# rov_control.net
KiCad netlist of a schematic drawn in EAGLE
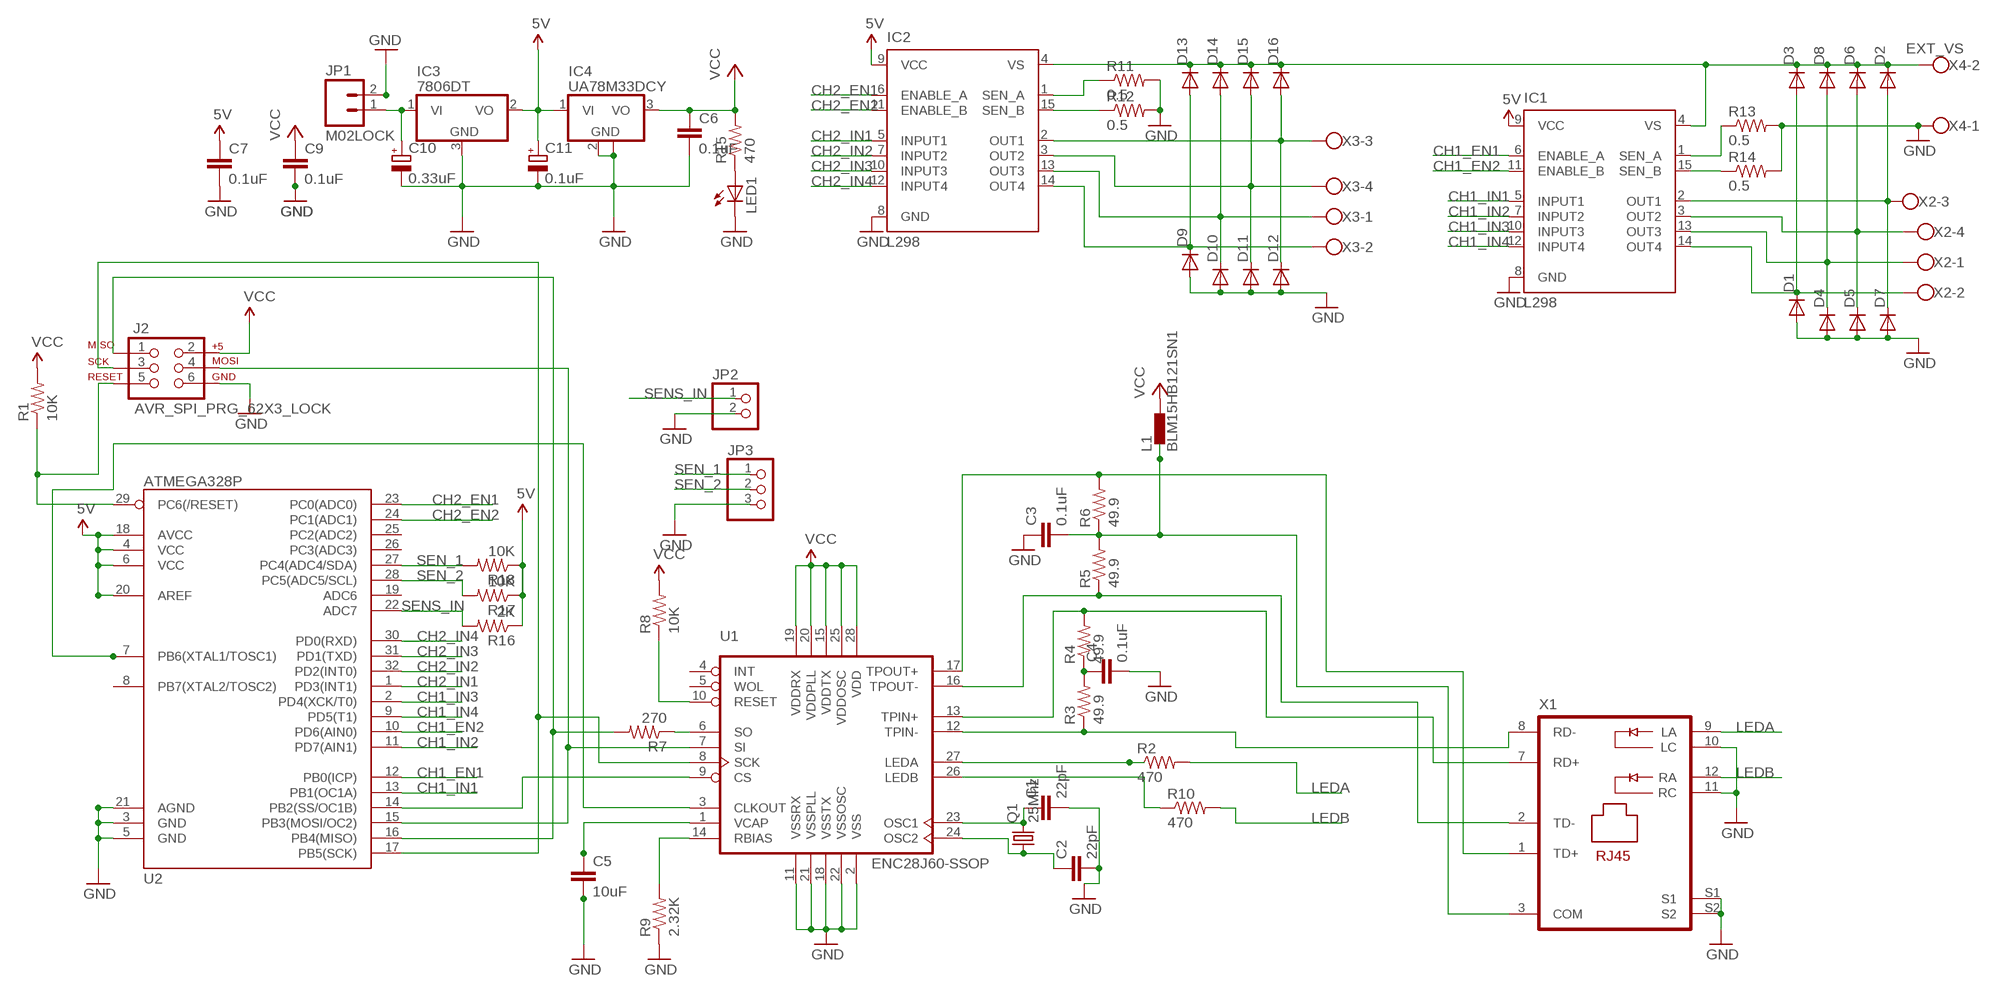
[diagram p0: schematic, sheet 1]

(export (version "E")
  (design (tool "Eeschema 10.0.6"))
  (components
    (comp (ref "C1")
      (value "22pF")
      (footprint "eagle-import:0805")
      (libsource (lib "eagle-import") (part "CAP0805"))
    )
    (comp (ref "C2")
      (value "22pF")
      (footprint "eagle-import:0805")
      (libsource (lib "eagle-import") (part "CAP0805"))
    )
    (comp (ref "C3")
      (value "0.1uF")
      (footprint "eagle-import:0805")
      (libsource (lib "eagle-import") (part "CAP0805"))
    )
    (comp (ref "C4")
      (value "0.1uF")
      (footprint "eagle-import:0805")
      (libsource (lib "eagle-import") (part "CAP0805"))
    )
    (comp (ref "C5")
      (value "10uF")
      (footprint "eagle-import:0805")
      (libsource (lib "eagle-import") (part "CAP0805"))
    )
    (comp (ref "C6")
      (value "0.1uF")
      (footprint "eagle-import:0805")
      (libsource (lib "eagle-import") (part "SparkFun-Passives_CAP0805"))
    )
    (comp (ref "C7")
      (value "0.1uF")
      (footprint "eagle-import:0805")
      (libsource (lib "eagle-import") (part "CAP0805"))
    )
    (comp (ref "C9")
      (value "0.1uF")
      (footprint "eagle-import:0805")
      (libsource (lib "eagle-import") (part "CAP0805"))
    )
    (comp (ref "C10")
      (value "0.33uF")
      (footprint "eagle-import:PANASONIC_A")
      (libsource (lib "eagle-import") (part "CPOL-EUA"))
    )
    (comp (ref "C11")
      (value "0.1uF")
      (footprint "eagle-import:PANASONIC_A")
      (libsource (lib "eagle-import") (part "CPOL-EUA"))
    )
    (comp (ref "D1")
      (value "DIODESMA")
      (footprint "eagle-import:SMA-DIODE")
      (libsource (lib "eagle-import") (part "DIODESMA"))
    )
    (comp (ref "D2")
      (value "DIODESMA")
      (footprint "eagle-import:SMA-DIODE")
      (libsource (lib "eagle-import") (part "DIODESMA"))
    )
    (comp (ref "D3")
      (value "DIODESMA")
      (footprint "eagle-import:SMA-DIODE")
      (libsource (lib "eagle-import") (part "DIODESMA"))
    )
    (comp (ref "D4")
      (value "DIODESMA")
      (footprint "eagle-import:SMA-DIODE")
      (libsource (lib "eagle-import") (part "DIODESMA"))
    )
    (comp (ref "D5")
      (value "DIODESMA")
      (footprint "eagle-import:SMA-DIODE")
      (libsource (lib "eagle-import") (part "DIODESMA"))
    )
    (comp (ref "D6")
      (value "DIODESMA")
      (footprint "eagle-import:SMA-DIODE")
      (libsource (lib "eagle-import") (part "DIODESMA"))
    )
    (comp (ref "D7")
      (value "DIODESMA")
      (footprint "eagle-import:SMA-DIODE")
      (libsource (lib "eagle-import") (part "DIODESMA"))
    )
    (comp (ref "D8")
      (value "DIODESMA")
      (footprint "eagle-import:SMA-DIODE")
      (libsource (lib "eagle-import") (part "DIODESMA"))
    )
    (comp (ref "D9")
      (value "DIODESMA")
      (footprint "eagle-import:SMA-DIODE")
      (libsource (lib "eagle-import") (part "DIODESMA"))
    )
    (comp (ref "D10")
      (value "DIODESMA")
      (footprint "eagle-import:SMA-DIODE")
      (libsource (lib "eagle-import") (part "DIODESMA"))
    )
    (comp (ref "D11")
      (value "DIODESMA")
      (footprint "eagle-import:SMA-DIODE")
      (libsource (lib "eagle-import") (part "DIODESMA"))
    )
    (comp (ref "D12")
      (value "DIODESMA")
      (footprint "eagle-import:SMA-DIODE")
      (libsource (lib "eagle-import") (part "DIODESMA"))
    )
    (comp (ref "D13")
      (value "DIODESMA")
      (footprint "eagle-import:SMA-DIODE")
      (libsource (lib "eagle-import") (part "DIODESMA"))
    )
    (comp (ref "D14")
      (value "DIODESMA")
      (footprint "eagle-import:SMA-DIODE")
      (libsource (lib "eagle-import") (part "DIODESMA"))
    )
    (comp (ref "D15")
      (value "DIODESMA")
      (footprint "eagle-import:SMA-DIODE")
      (libsource (lib "eagle-import") (part "DIODESMA"))
    )
    (comp (ref "D16")
      (value "DIODESMA")
      (footprint "eagle-import:SMA-DIODE")
      (libsource (lib "eagle-import") (part "DIODESMA"))
    )
    (comp (ref "IC1")
      (value "L298")
      (footprint "eagle-import:MULTIWATT-15")
      (fields (field (name "MPN") "L298N"))
      (libsource (lib "eagle-import") (part "L298"))
    )
    (comp (ref "IC2")
      (value "L298")
      (footprint "eagle-import:MULTIWATT-15")
      (fields (field (name "MPN") "L298N"))
      (libsource (lib "eagle-import") (part "L298"))
    )
    (comp (ref "IC3")
      (value "7806DT")
      (footprint "eagle-import:TO252")
      (libsource (lib "eagle-import") (part "78DT06"))
    )
    (comp (ref "IC4")
      (value "UA78M33DCY")
      (footprint "eagle-import:SOT223")
      (libsource (lib "eagle-import") (part "UA78MDCY33"))
    )
    (comp (ref "J2")
      (value "AVR_SPI_PRG_62X3_LOCK")
      (footprint "eagle-import:2X3_LOCK")
      (libsource (lib "eagle-import") (part "AVR_SPI_PRG_62X3_LOCK"))
    )
    (comp (ref "JP1")
      (value "M02LOCK")
      (footprint "eagle-import:1X02_LOCK")
      (libsource (lib "eagle-import") (part "M02LOCK"))
    )
    (comp (ref "JP2")
      (value "PINHD-1X2")
      (footprint "eagle-import:1X02")
      (libsource (lib "eagle-import") (part "PINHD-1X2"))
    )
    (comp (ref "JP3")
      (value "PINHD-1X3")
      (footprint "eagle-import:1X03")
      (libsource (lib "eagle-import") (part "PINHD-1X3"))
    )
    (comp (ref "L1")
      (value "BLM15HB121SN1")
      (footprint "eagle-import:0402")
      (libsource (lib "eagle-import") (part "BLM15HB121SN1"))
    )
    (comp (ref "LED1")
      (value "LEDSML0805")
      (footprint "eagle-import:SML0805")
      (libsource (lib "eagle-import") (part "LEDSML0805"))
    )
    (comp (ref "Q1")
      (value "25Mhz")
      (footprint "eagle-import:HC49UP")
      (libsource (lib "eagle-import") (part "CRYSTALHC49UP"))
    )
    (comp (ref "R1")
      (value "10K")
      (footprint "eagle-import:0805")
      (libsource (lib "eagle-import") (part "SparkFun-Resistors_RESISTOR0805-RES"))
    )
    (comp (ref "R2")
      (value "470")
      (footprint "eagle-import:0805")
      (libsource (lib "eagle-import") (part "RESISTOR0805-RES"))
    )
    (comp (ref "R3")
      (value "49.9")
      (footprint "eagle-import:0805")
      (libsource (lib "eagle-import") (part "SparkFun-Resistors_RESISTOR0805-RES"))
    )
    (comp (ref "R4")
      (value "49.9")
      (footprint "eagle-import:0805")
      (libsource (lib "eagle-import") (part "SparkFun-Resistors_RESISTOR0805-RES"))
    )
    (comp (ref "R5")
      (value "49.9")
      (footprint "eagle-import:0805")
      (libsource (lib "eagle-import") (part "RESISTOR0805-RES"))
    )
    (comp (ref "R6")
      (value "49.9")
      (footprint "eagle-import:0805")
      (libsource (lib "eagle-import") (part "RESISTOR0805-RES"))
    )
    (comp (ref "R7")
      (value "270")
      (footprint "eagle-import:0805")
      (libsource (lib "eagle-import") (part "SparkFun-Resistors_RESISTOR0805-RES"))
    )
    (comp (ref "R8")
      (value "10K")
      (footprint "eagle-import:0805")
      (libsource (lib "eagle-import") (part "RESISTOR0805-RES"))
    )
    (comp (ref "R9")
      (value "2.32K")
      (footprint "eagle-import:0805")
      (libsource (lib "eagle-import") (part "RESISTOR0805-RES"))
    )
    (comp (ref "R10")
      (value "470")
      (footprint "eagle-import:0805")
      (libsource (lib "eagle-import") (part "RESISTOR0805-RES"))
    )
    (comp (ref "R11")
      (value "0.5")
      (footprint "eagle-import:0805")
      (libsource (lib "eagle-import") (part "RESISTOR0805-RES"))
    )
    (comp (ref "R12")
      (value "0.5")
      (footprint "eagle-import:0805")
      (libsource (lib "eagle-import") (part "RESISTOR0805-RES"))
    )
    (comp (ref "R13")
      (value "0.5")
      (footprint "eagle-import:0805")
      (libsource (lib "eagle-import") (part "RESISTOR0805-RES"))
    )
    (comp (ref "R14")
      (value "0.5")
      (footprint "eagle-import:0805")
      (libsource (lib "eagle-import") (part "RESISTOR0805-RES"))
    )
    (comp (ref "R15")
      (value "470")
      (footprint "eagle-import:0805")
      (libsource (lib "eagle-import") (part "RESISTOR0805-RES"))
    )
    (comp (ref "R16")
      (value "2K")
      (footprint "eagle-import:0805")
      (libsource (lib "eagle-import") (part "SparkFun-Resistors_RESISTOR0805-RES"))
    )
    (comp (ref "R17")
      (value "10K")
      (footprint "eagle-import:0805")
      (libsource (lib "eagle-import") (part "SparkFun-Resistors_RESISTOR0805-RES"))
    )
    (comp (ref "R18")
      (value "10K")
      (footprint "eagle-import:0805")
      (libsource (lib "eagle-import") (part "SparkFun-Resistors_RESISTOR0805-RES"))
    )
    (comp (ref "U1")
      (value "ENC28J60-SSOP")
      (footprint "eagle-import:SSOP28")
      (libsource (lib "eagle-import") (part "ENC28J60-SSOP"))
    )
    (comp (ref "U2")
      (value "ATMEGA328P")
      (footprint "eagle-import:TQFP32-08")
      (libsource (lib "eagle-import") (part "ATMEGA328_SMT"))
    )
    (comp (ref "X1")
      (value "LU1T041X")
      (footprint "eagle-import:PJ-J0")
      (libsource (lib "eagle-import") (part "LU1T041X"))
    )
    (comp (ref "X2")
      (value "W237-4")
      (footprint "eagle-import:W237-4")
      (libsource (lib "eagle-import") (part "W237-4"))
    )
    (comp (ref "X3")
      (value "W237-4")
      (footprint "eagle-import:W237-4")
      (libsource (lib "eagle-import") (part "W237-4"))
    )
    (comp (ref "X4")
      (value "EXT_VS")
      (footprint "eagle-import:W237-102")
      (fields (field (name "MPN") "237-102"))
      (libsource (lib "eagle-import") (part "W237-102"))
    )
  )
  (nets
    (net (code "1") (name "/CH1_EN1") (class "Default")
      (node (ref "IC1") (pin "6") (pinfunction "ENABLE_A_6") (pintype "input"))
      (node (ref "U2") (pin "12") (pinfunction "PB0(ICP)_12") (pintype "bidirectional"))
    )
    (net (code "2") (name "/CH1_EN2") (class "Default")
      (node (ref "IC1") (pin "11") (pinfunction "ENABLE_B_11") (pintype "input"))
      (node (ref "U2") (pin "10") (pinfunction "PD6(AIN0)_10") (pintype "bidirectional"))
    )
    (net (code "3") (name "/CH1_IN1") (class "Default")
      (node (ref "IC1") (pin "5") (pinfunction "INPUT1_5") (pintype "input"))
      (node (ref "U2") (pin "13") (pinfunction "PB1(OC1A)_13") (pintype "bidirectional"))
    )
    (net (code "4") (name "/CH1_IN2") (class "Default")
      (node (ref "IC1") (pin "7") (pinfunction "INPUT2_7") (pintype "input"))
      (node (ref "U2") (pin "11") (pinfunction "PD7(AIN1)_11") (pintype "bidirectional"))
    )
    (net (code "5") (name "/CH1_IN3") (class "Default")
      (node (ref "IC1") (pin "10") (pinfunction "INPUT3_10") (pintype "input"))
      (node (ref "U2") (pin "2") (pinfunction "PD4(XCK/T0)_2") (pintype "bidirectional"))
    )
    (net (code "6") (name "/CH1_IN4") (class "Default")
      (node (ref "IC1") (pin "12") (pinfunction "INPUT4_12") (pintype "input"))
      (node (ref "U2") (pin "9") (pinfunction "PD5(T1)_9") (pintype "bidirectional"))
    )
    (net (code "7") (name "/CH2_EN1") (class "Default")
      (node (ref "IC2") (pin "6") (pinfunction "ENABLE_A_6") (pintype "input"))
      (node (ref "U2") (pin "23") (pinfunction "PC0(ADC0)_23") (pintype "bidirectional"))
    )
    (net (code "8") (name "/CH2_EN2") (class "Default")
      (node (ref "IC2") (pin "11") (pinfunction "ENABLE_B_11") (pintype "input"))
      (node (ref "U2") (pin "24") (pinfunction "PC1(ADC1)_24") (pintype "bidirectional"))
    )
    (net (code "9") (name "/CH2_IN1") (class "Default")
      (node (ref "IC2") (pin "5") (pinfunction "INPUT1_5") (pintype "input"))
      (node (ref "U2") (pin "1") (pinfunction "PD3(INT1)_1") (pintype "bidirectional"))
    )
    (net (code "10") (name "/CH2_IN2") (class "Default")
      (node (ref "IC2") (pin "7") (pinfunction "INPUT2_7") (pintype "input"))
      (node (ref "U2") (pin "32") (pinfunction "PD2(INT0)_32") (pintype "bidirectional"))
    )
    (net (code "11") (name "/CH2_IN3") (class "Default")
      (node (ref "IC2") (pin "10") (pinfunction "INPUT3_10") (pintype "input"))
      (node (ref "U2") (pin "31") (pinfunction "PD1(TXD)_31") (pintype "bidirectional"))
    )
    (net (code "12") (name "/CH2_IN4") (class "Default")
      (node (ref "IC2") (pin "12") (pinfunction "INPUT4_12") (pintype "input"))
      (node (ref "U2") (pin "30") (pinfunction "PD0(RXD)_30") (pintype "bidirectional"))
    )
    (net (code "13") (name "/LEDA") (class "Default")
      (node (ref "R2") (pin "2") (pinfunction "2_2") (pintype "passive"))
      (node (ref "X1") (pin "9") (pinfunction "LA_9") (pintype "passive"))
    )
    (net (code "14") (name "/LEDB") (class "Default")
      (node (ref "R10") (pin "2") (pinfunction "2_2") (pintype "passive"))
      (node (ref "X1") (pin "12") (pinfunction "RA_12") (pintype "passive"))
    )
    (net (code "15") (name "/SENS_IN") (class "Default")
      (node (ref "JP2") (pin "1") (pinfunction "1_1") (pintype "passive"))
      (node (ref "R16") (pin "2") (pinfunction "2_2") (pintype "passive"))
      (node (ref "U2") (pin "22") (pinfunction "ADC7_22") (pintype "bidirectional"))
    )
    (net (code "16") (name "/SEN_1") (class "Default")
      (node (ref "JP3") (pin "1") (pinfunction "1_1") (pintype "passive"))
      (node (ref "R18") (pin "2") (pinfunction "2_2") (pintype "passive"))
      (node (ref "U2") (pin "27") (pinfunction "PC4(ADC4/SDA)_27") (pintype "bidirectional"))
    )
    (net (code "17") (name "/SEN_2") (class "Default")
      (node (ref "JP3") (pin "2") (pinfunction "2_2") (pintype "passive"))
      (node (ref "R17") (pin "2") (pinfunction "2_2") (pintype "passive"))
      (node (ref "U2") (pin "28") (pinfunction "PC5(ADC5/SCL)_28") (pintype "bidirectional"))
    )
    (net (code "18") (name "5V") (class "Default")
      (node (ref "C11") (pin "+") (pinfunction "+_+") (pintype "passive"))
      (node (ref "C7") (pin "1") (pinfunction "1_1") (pintype "passive"))
      (node (ref "IC1") (pin "9") (pinfunction "VCC_9") (pintype "power_in"))
      (node (ref "IC2") (pin "9") (pinfunction "VCC_9") (pintype "power_in"))
      (node (ref "IC3") (pin "2") (pinfunction "VO_2") (pintype "passive"))
      (node (ref "IC4") (pin "1") (pinfunction "VI_1") (pintype "input"))
      (node (ref "R16") (pin "1") (pinfunction "1_1") (pintype "passive"))
      (node (ref "R17") (pin "1") (pinfunction "1_1") (pintype "passive"))
      (node (ref "R18") (pin "1") (pinfunction "1_1") (pintype "passive"))
      (node (ref "U2") (pin "18") (pinfunction "AVCC_18") (pintype "bidirectional"))
      (node (ref "U2") (pin "20") (pinfunction "AREF_20") (pintype "bidirectional"))
      (node (ref "U2") (pin "4") (pinfunction "VCC_4") (pintype "bidirectional"))
      (node (ref "U2") (pin "6") (pinfunction "VCC_6") (pintype "bidirectional"))
    )
    (net (code "19") (name "GND") (class "Default")
      (node (ref "C1") (pin "2") (pinfunction "2_2") (pintype "passive"))
      (node (ref "C10") (pin "-") (pinfunction "-_-") (pintype "passive"))
      (node (ref "C11") (pin "-") (pinfunction "-_-") (pintype "passive"))
      (node (ref "C2") (pin "2") (pinfunction "2_2") (pintype "passive"))
      (node (ref "C3") (pin "1") (pinfunction "1_1") (pintype "passive"))
      (node (ref "C4") (pin "2") (pinfunction "2_2") (pintype "passive"))
      (node (ref "C5") (pin "2") (pinfunction "2_2") (pintype "passive"))
      (node (ref "C6") (pin "2") (pinfunction "2_2") (pintype "passive"))
      (node (ref "C7") (pin "2") (pinfunction "2_2") (pintype "passive"))
      (node (ref "C9") (pin "2") (pinfunction "2_2") (pintype "passive"))
      (node (ref "D1") (pin "A") (pinfunction "A_A") (pintype "passive"))
      (node (ref "D10") (pin "A") (pinfunction "A_A") (pintype "passive"))
      (node (ref "D11") (pin "A") (pinfunction "A_A") (pintype "passive"))
      (node (ref "D12") (pin "A") (pinfunction "A_A") (pintype "passive"))
      (node (ref "D4") (pin "A") (pinfunction "A_A") (pintype "passive"))
      (node (ref "D5") (pin "A") (pinfunction "A_A") (pintype "passive"))
      (node (ref "D7") (pin "A") (pinfunction "A_A") (pintype "passive"))
      (node (ref "D9") (pin "A") (pinfunction "A_A") (pintype "passive"))
      (node (ref "IC1") (pin "8") (pinfunction "GND_8") (pintype "power_in"))
      (node (ref "IC2") (pin "8") (pinfunction "GND_8") (pintype "power_in"))
      (node (ref "IC3") (pin "3") (pinfunction "GND_3") (pintype "passive"))
      (node (ref "IC4") (pin "2") (pinfunction "GND_2") (pintype "passive"))
      (node (ref "IC4") (pin "4") (pinfunction "GND_4") (pintype "passive"))
      (node (ref "J2") (pin "6") (pinfunction "6_6") (pintype "passive"))
      (node (ref "JP1") (pin "2") (pinfunction "2_2") (pintype "passive"))
      (node (ref "JP2") (pin "2") (pinfunction "2_2") (pintype "passive"))
      (node (ref "JP3") (pin "3") (pinfunction "3_3") (pintype "passive"))
      (node (ref "LED1") (pin "C") (pinfunction "C_C") (pintype "passive"))
      (node (ref "R11") (pin "2") (pinfunction "2_2") (pintype "passive"))
      (node (ref "R12") (pin "2") (pinfunction "2_2") (pintype "passive"))
      (node (ref "R13") (pin "2") (pinfunction "2_2") (pintype "passive"))
      (node (ref "R14") (pin "2") (pinfunction "2_2") (pintype "passive"))
      (node (ref "R9") (pin "1") (pinfunction "1_1") (pintype "passive"))
      (node (ref "U1") (pin "11") (pinfunction "VSSRX_11") (pintype "power_in"))
      (node (ref "U1") (pin "18") (pinfunction "VSSTX_18") (pintype "power_in"))
      (node (ref "U1") (pin "2") (pinfunction "VSS_2") (pintype "power_in"))
      (node (ref "U1") (pin "21") (pinfunction "VSSPLL_21") (pintype "power_in"))
      (node (ref "U1") (pin "22") (pinfunction "VSSOSC_22") (pintype "power_in"))
      (node (ref "U2") (pin "21") (pinfunction "AGND_21") (pintype "bidirectional"))
      (node (ref "U2") (pin "3") (pinfunction "GND_3") (pintype "bidirectional"))
      (node (ref "U2") (pin "5") (pinfunction "GND_5") (pintype "bidirectional"))
      (node (ref "X1") (pin "10") (pinfunction "LC_10") (pintype "passive"))
      (node (ref "X1") (pin "11") (pinfunction "RC_11") (pintype "passive"))
      (node (ref "X1") (pin "S1") (pinfunction "S1_S1") (pintype "passive"))
      (node (ref "X1") (pin "S2") (pinfunction "S2_S2") (pintype "passive"))
      (node (ref "X4") (pin "1") (pinfunction "KL_1") (pintype "passive"))
    )
    (net (code "20") (name "Net-(C4-Pad1)") (class "Default")
      (node (ref "C4") (pin "1") (pinfunction "1_1") (pintype "passive"))
      (node (ref "R3") (pin "2") (pinfunction "2_2") (pintype "passive"))
      (node (ref "R4") (pin "1") (pinfunction "1_1") (pintype "passive"))
    )
    (net (code "21") (name "Net-(IC1-OUT1)") (class "Default")
      (node (ref "D2") (pin "A") (pinfunction "A_A") (pintype "passive"))
      (node (ref "D7") (pin "C") (pinfunction "C_C") (pintype "passive"))
      (node (ref "IC1") (pin "2") (pinfunction "OUT1_2") (pintype "output"))
      (node (ref "X2") (pin "3") (pinfunction "KL_3") (pintype "passive"))
    )
    (net (code "22") (name "Net-(IC1-OUT2)") (class "Default")
      (node (ref "D5") (pin "C") (pinfunction "C_C") (pintype "passive"))
      (node (ref "D6") (pin "A") (pinfunction "A_A") (pintype "passive"))
      (node (ref "IC1") (pin "3") (pinfunction "OUT2_3") (pintype "output"))
      (node (ref "X2") (pin "4") (pinfunction "KL_4") (pintype "passive"))
    )
    (net (code "23") (name "Net-(IC1-OUT3)") (class "Default")
      (node (ref "D4") (pin "C") (pinfunction "C_C") (pintype "passive"))
      (node (ref "D8") (pin "A") (pinfunction "A_A") (pintype "passive"))
      (node (ref "IC1") (pin "13") (pinfunction "OUT3_13") (pintype "output"))
      (node (ref "X2") (pin "1") (pinfunction "KL_1") (pintype "passive"))
    )
    (net (code "24") (name "Net-(IC1-OUT4)") (class "Default")
      (node (ref "D1") (pin "C") (pinfunction "C_C") (pintype "passive"))
      (node (ref "D3") (pin "A") (pinfunction "A_A") (pintype "passive"))
      (node (ref "IC1") (pin "14") (pinfunction "OUT4_14") (pintype "output"))
      (node (ref "X2") (pin "2") (pinfunction "KL_2") (pintype "passive"))
    )
    (net (code "25") (name "Net-(IC1-SEN_A)") (class "Default")
      (node (ref "IC1") (pin "1") (pinfunction "SEN_A_1") (pintype "input"))
      (node (ref "R13") (pin "1") (pinfunction "1_1") (pintype "passive"))
    )
    (net (code "26") (name "Net-(IC1-SEN_B)") (class "Default")
      (node (ref "IC1") (pin "15") (pinfunction "SEN_B_15") (pintype "input"))
      (node (ref "R14") (pin "1") (pinfunction "1_1") (pintype "passive"))
    )
    (net (code "27") (name "Net-(IC1-VS)") (class "Default")
      (node (ref "D13") (pin "C") (pinfunction "C_C") (pintype "passive"))
      (node (ref "D14") (pin "C") (pinfunction "C_C") (pintype "passive"))
      (node (ref "D15") (pin "C") (pinfunction "C_C") (pintype "passive"))
      (node (ref "D16") (pin "C") (pinfunction "C_C") (pintype "passive"))
      (node (ref "D2") (pin "C") (pinfunction "C_C") (pintype "passive"))
      (node (ref "D3") (pin "C") (pinfunction "C_C") (pintype "passive"))
      (node (ref "D6") (pin "C") (pinfunction "C_C") (pintype "passive"))
      (node (ref "D8") (pin "C") (pinfunction "C_C") (pintype "passive"))
      (node (ref "IC1") (pin "4") (pinfunction "VS_4") (pintype "power_in"))
      (node (ref "IC2") (pin "4") (pinfunction "VS_4") (pintype "power_in"))
      (node (ref "X4") (pin "2") (pinfunction "KL_2") (pintype "passive"))
    )
    (net (code "28") (name "Net-(IC2-OUT1)") (class "Default")
      (node (ref "D12") (pin "C") (pinfunction "C_C") (pintype "passive"))
      (node (ref "D16") (pin "A") (pinfunction "A_A") (pintype "passive"))
      (node (ref "IC2") (pin "2") (pinfunction "OUT1_2") (pintype "output"))
      (node (ref "X3") (pin "3") (pinfunction "KL_3") (pintype "passive"))
    )
    (net (code "29") (name "Net-(IC2-OUT2)") (class "Default")
      (node (ref "D11") (pin "C") (pinfunction "C_C") (pintype "passive"))
      (node (ref "D15") (pin "A") (pinfunction "A_A") (pintype "passive"))
      (node (ref "IC2") (pin "3") (pinfunction "OUT2_3") (pintype "output"))
      (node (ref "X3") (pin "4") (pinfunction "KL_4") (pintype "passive"))
    )
    (net (code "30") (name "Net-(IC2-OUT3)") (class "Default")
      (node (ref "D10") (pin "C") (pinfunction "C_C") (pintype "passive"))
      (node (ref "D14") (pin "A") (pinfunction "A_A") (pintype "passive"))
      (node (ref "IC2") (pin "13") (pinfunction "OUT3_13") (pintype "output"))
      (node (ref "X3") (pin "1") (pinfunction "KL_1") (pintype "passive"))
    )
    (net (code "31") (name "Net-(IC2-OUT4)") (class "Default")
      (node (ref "D13") (pin "A") (pinfunction "A_A") (pintype "passive"))
      (node (ref "D9") (pin "C") (pinfunction "C_C") (pintype "passive"))
      (node (ref "IC2") (pin "14") (pinfunction "OUT4_14") (pintype "output"))
      (node (ref "X3") (pin "2") (pinfunction "KL_2") (pintype "passive"))
    )
    (net (code "32") (name "Net-(IC2-SEN_A)") (class "Default")
      (node (ref "IC2") (pin "1") (pinfunction "SEN_A_1") (pintype "input"))
      (node (ref "R11") (pin "1") (pinfunction "1_1") (pintype "passive"))
    )
    (net (code "33") (name "Net-(IC2-SEN_B)") (class "Default")
      (node (ref "IC2") (pin "15") (pinfunction "SEN_B_15") (pintype "input"))
      (node (ref "R12") (pin "1") (pinfunction "1_1") (pintype "passive"))
    )
    (net (code "34") (name "Net-(IC3-VI)") (class "Default")
      (node (ref "C10") (pin "+") (pinfunction "+_+") (pintype "passive"))
      (node (ref "IC3") (pin "1") (pinfunction "VI_1") (pintype "input"))
      (node (ref "JP1") (pin "1") (pinfunction "1_1") (pintype "passive"))
    )
    (net (code "35") (name "Net-(LED1-PadA)") (class "Default")
      (node (ref "LED1") (pin "A") (pinfunction "A_A") (pintype "passive"))
      (node (ref "R15") (pin "1") (pinfunction "1_1") (pintype "passive"))
    )
    (net (code "36") (name "Net-(U1-CLKOUT)") (class "Default")
      (node (ref "U1") (pin "3") (pinfunction "CLKOUT_3") (pintype "output"))
      (node (ref "U2") (pin "7") (pinfunction "PB6(XTAL1/TOSC1)_7") (pintype "bidirectional"))
    )
    (net (code "37") (name "Net-(U1-CS)") (class "Default")
      (node (ref "U1") (pin "9") (pinfunction "CS_9") (pintype "input"))
      (node (ref "U2") (pin "14") (pinfunction "PB2(SS/OC1B)_14") (pintype "bidirectional"))
    )
    (net (code "38") (name "Net-(U1-LEDA)") (class "Default")
      (node (ref "R2") (pin "1") (pinfunction "1_1") (pintype "passive"))
      (node (ref "U1") (pin "27") (pinfunction "LEDA_27") (pintype "output"))
    )
    (net (code "39") (name "Net-(U1-LEDB)") (class "Default")
      (node (ref "R10") (pin "1") (pinfunction "1_1") (pintype "passive"))
      (node (ref "U1") (pin "26") (pinfunction "LEDB_26") (pintype "output"))
    )
    (net (code "40") (name "Net-(U1-OSC1)") (class "Default")
      (node (ref "C1") (pin "1") (pinfunction "1_1") (pintype "passive"))
      (node (ref "Q1") (pin "2") (pinfunction "2_2") (pintype "passive"))
      (node (ref "U1") (pin "23") (pinfunction "OSC1_23") (pintype "input"))
    )
    (net (code "41") (name "Net-(U1-OSC2)") (class "Default")
      (node (ref "C2") (pin "1") (pinfunction "1_1") (pintype "passive"))
      (node (ref "Q1") (pin "1") (pinfunction "1_1") (pintype "passive"))
      (node (ref "U1") (pin "24") (pinfunction "OSC2_24") (pintype "output"))
    )
    (net (code "42") (name "Net-(U1-RBIAS)") (class "Default")
      (node (ref "R9") (pin "2") (pinfunction "2_2") (pintype "passive"))
      (node (ref "U1") (pin "14") (pinfunction "RBIAS_14") (pintype "passive"))
    )
    (net (code "43") (name "Net-(U1-RESET)") (class "Default")
      (node (ref "R8") (pin "1") (pinfunction "1_1") (pintype "passive"))
      (node (ref "U1") (pin "10") (pinfunction "RESET_10") (pintype "input"))
    )
    (net (code "44") (name "Net-(U1-SCK)") (class "Default")
      (node (ref "J2") (pin "3") (pinfunction "3_3") (pintype "passive"))
      (node (ref "U1") (pin "8") (pinfunction "SCK_8") (pintype "input"))
      (node (ref "U2") (pin "17") (pinfunction "PB5(SCK)_17") (pintype "bidirectional"))
    )
    (net (code "45") (name "Net-(U1-SI)") (class "Default")
      (node (ref "J2") (pin "4") (pinfunction "4_4") (pintype "passive"))
      (node (ref "U1") (pin "7") (pinfunction "SI_7") (pintype "input"))
      (node (ref "U2") (pin "15") (pinfunction "PB3(MOSI/OC2)_15") (pintype "bidirectional"))
    )
    (net (code "46") (name "Net-(U1-SO)") (class "Default")
      (node (ref "R7") (pin "1") (pinfunction "1_1") (pintype "passive"))
      (node (ref "U1") (pin "6") (pinfunction "SO_6") (pintype "output"))
    )
    (net (code "47") (name "Net-(U1-TPIN+)") (class "Default")
      (node (ref "R4") (pin "2") (pinfunction "2_2") (pintype "passive"))
      (node (ref "U1") (pin "13") (pinfunction "TPIN+_13") (pintype "input"))
      (node (ref "X1") (pin "7") (pinfunction "RD+_7") (pintype "bidirectional"))
    )
    (net (code "48") (name "Net-(U1-TPIN-)") (class "Default")
      (node (ref "R3") (pin "1") (pinfunction "1_1") (pintype "passive"))
      (node (ref "U1") (pin "12") (pinfunction "TPIN-_12") (pintype "input"))
      (node (ref "X1") (pin "8") (pinfunction "RD-_8") (pintype "bidirectional"))
    )
    (net (code "49") (name "Net-(U1-TPOUT+)") (class "Default")
      (node (ref "R6") (pin "2") (pinfunction "2_2") (pintype "passive"))
      (node (ref "U1") (pin "17") (pinfunction "TPOUT+_17") (pintype "output"))
      (node (ref "X1") (pin "1") (pinfunction "TD+_1") (pintype "bidirectional"))
    )
    (net (code "50") (name "Net-(U1-TPOUT-)") (class "Default")
      (node (ref "R5") (pin "1") (pinfunction "1_1") (pintype "passive"))
      (node (ref "U1") (pin "16") (pinfunction "TPOUT-_16") (pintype "output"))
      (node (ref "X1") (pin "2") (pinfunction "TD-_2") (pintype "bidirectional"))
    )
    (net (code "51") (name "Net-(U1-VCAP)") (class "Default")
      (node (ref "C5") (pin "1") (pinfunction "1_1") (pintype "passive"))
      (node (ref "U1") (pin "1") (pinfunction "VCAP_1") (pintype "power_in"))
    )
    (net (code "52") (name "Net-(U2-PB4(MISO))") (class "Default")
      (node (ref "J2") (pin "1") (pinfunction "1_1") (pintype "passive"))
      (node (ref "R7") (pin "2") (pinfunction "2_2") (pintype "passive"))
      (node (ref "U2") (pin "16") (pinfunction "PB4(MISO)_16") (pintype "bidirectional"))
    )
    (net (code "53") (name "Net-(U2-PC6({slash}RESET))") (class "Default")
      (node (ref "J2") (pin "5") (pinfunction "5_5") (pintype "passive"))
      (node (ref "R1") (pin "1") (pinfunction "1_1") (pintype "passive"))
      (node (ref "U2") (pin "29") (pinfunction "PC6(/RESET)_29") (pintype "bidirectional"))
    )
    (net (code "54") (name "Net-(X1-COM)") (class "Default")
      (node (ref "C3") (pin "2") (pinfunction "2_2") (pintype "passive"))
      (node (ref "L1") (pin "1") (pinfunction "1_1") (pintype "passive"))
      (node (ref "R5") (pin "2") (pinfunction "2_2") (pintype "passive"))
      (node (ref "R6") (pin "1") (pinfunction "1_1") (pintype "passive"))
      (node (ref "X1") (pin "3") (pinfunction "COM_3") (pintype "bidirectional"))
    )
    (net (code "55") (name "VCC") (class "Default")
      (node (ref "C6") (pin "1") (pinfunction "1_1") (pintype "passive"))
      (node (ref "C9") (pin "1") (pinfunction "1_1") (pintype "passive"))
      (node (ref "IC4") (pin "3") (pinfunction "VO_3") (pintype "passive"))
      (node (ref "J2") (pin "2") (pinfunction "2_2") (pintype "passive"))
      (node (ref "L1") (pin "2") (pinfunction "2_2") (pintype "passive"))
      (node (ref "R1") (pin "2") (pinfunction "2_2") (pintype "passive"))
      (node (ref "R15") (pin "2") (pinfunction "2_2") (pintype "passive"))
      (node (ref "R8") (pin "2") (pinfunction "2_2") (pintype "passive"))
      (node (ref "U1") (pin "15") (pinfunction "VDDTX_15") (pintype "power_in"))
      (node (ref "U1") (pin "19") (pinfunction "VDDRX_19") (pintype "power_in"))
      (node (ref "U1") (pin "20") (pinfunction "VDDPLL_20") (pintype "power_in"))
      (node (ref "U1") (pin "25") (pinfunction "VDDOSC_25") (pintype "power_in"))
      (node (ref "U1") (pin "28") (pinfunction "VDD_28") (pintype "power_in"))
    )
    (net (code "56") (name "unconnected-(U1-INT-Pad4)") (class "Default")
      (node (ref "U1") (pin "4") (pinfunction "INT_4") (pintype "output"))
    )
    (net (code "57") (name "unconnected-(U1-WOL-Pad5)") (class "Default")
      (node (ref "U1") (pin "5") (pinfunction "WOL_5") (pintype "output"))
    )
    (net (code "58") (name "unconnected-(U2-ADC6-Pad19)") (class "Default")
      (node (ref "U2") (pin "19") (pinfunction "ADC6_19") (pintype "bidirectional"))
    )
    (net (code "59") (name "unconnected-(U2-PB7(XTAL2{slash}TOSC2)-Pad8)") (class "Default")
      (node (ref "U2") (pin "8") (pinfunction "PB7(XTAL2/TOSC2)_8") (pintype "bidirectional"))
    )
    (net (code "60") (name "unconnected-(U2-PC2(ADC2)-Pad25)") (class "Default")
      (node (ref "U2") (pin "25") (pinfunction "PC2(ADC2)_25") (pintype "bidirectional"))
    )
    (net (code "61") (name "unconnected-(U2-PC3(ADC3)-Pad26)") (class "Default")
      (node (ref "U2") (pin "26") (pinfunction "PC3(ADC3)_26") (pintype "bidirectional"))
    )
  )
)
